# Power.net
KiCad netlist of a schematic drawn in Altium Designer
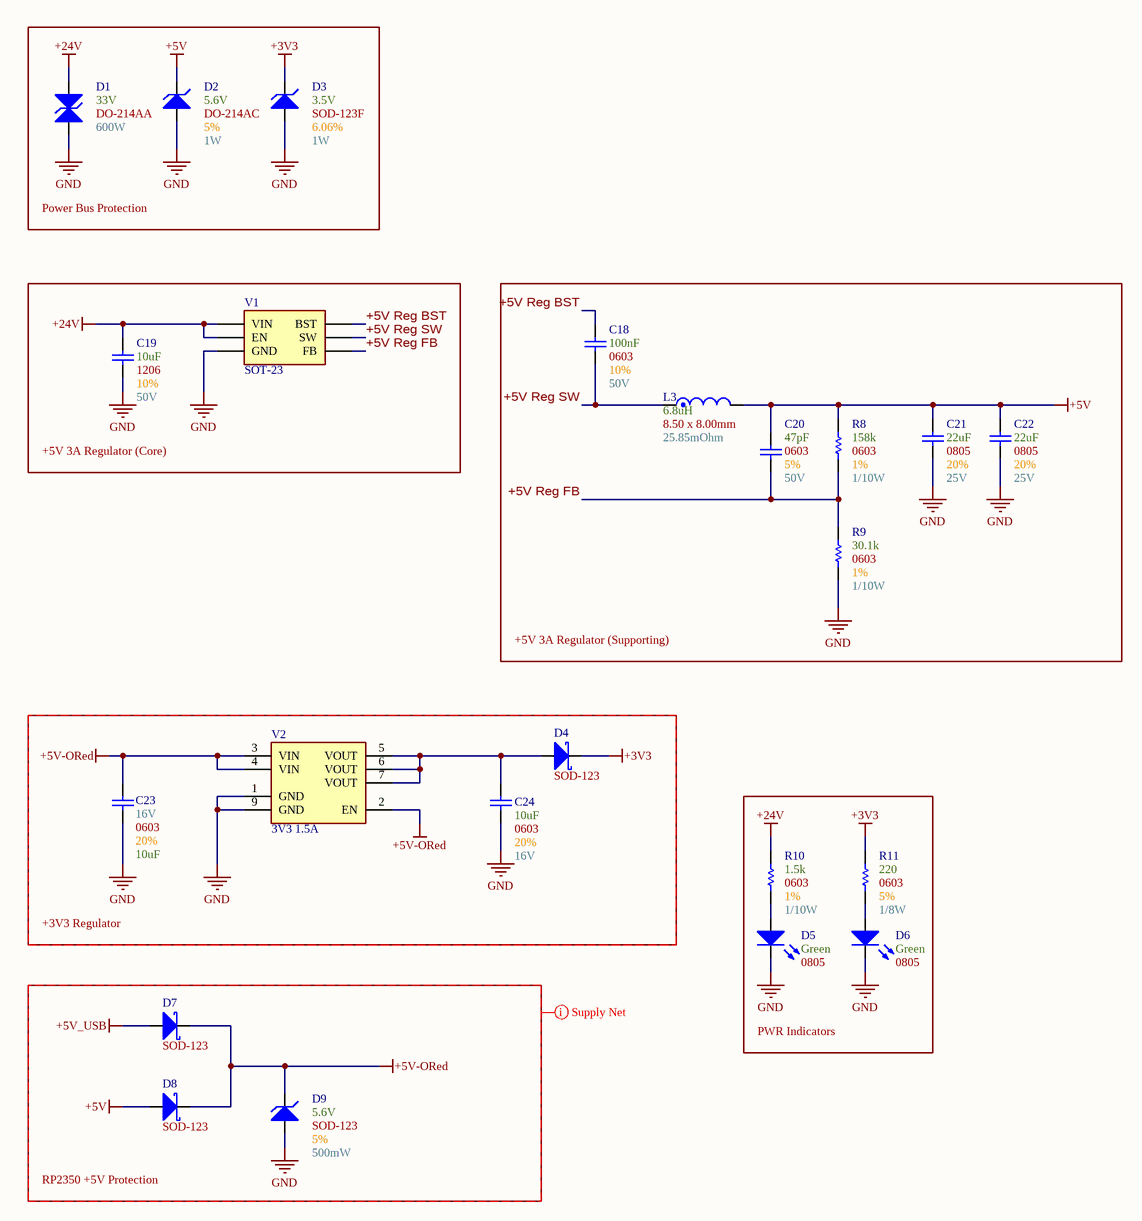
[diagram p0: Power.SchDoc]

(export (version "E")
  (design (tool "Eeschema 10.0.6"))
  (components
    (comp (ref "C18")
      (value "[Cap] 0603 0.1uF 10% 50V")
      (footprint "[Cap] SMD 0603")
      (description "CL10B104KB8NNNC")
      (fields
        (field (name "MAX VOLTAGE") "50V")
        (field (name "SIZE PACKAGE") "0603")
        (field (name "TOLERANCE") "10%")
        (field (name "CAPACITANCE") "100nF")
      )
      (libsource (lib "Capacitors") (part "[Cap] 0603 0.1uF 10% 50V"))
    )
    (comp (ref "C19")
      (value "[Cap] 1206 10uF 20% 50V")
      (footprint "[Cap] SMD 1206")
      (description "CGA5L3X5R1H106M160AB")
      (fields
        (field (name "MAX VOLTAGE") "50V")
        (field (name "SIZE PACKAGE") "1206")
        (field (name "TOLERANCE") "10%")
        (field (name "CAPACITANCE") "10uF")
      )
      (libsource (lib "Capacitors") (part "[Cap] 1206 10uF 20% 50V"))
    )
    (comp (ref "C20")
      (value "[Cap] 0603 47pF 5% 50V")
      (footprint "[Cap] SMD 0603")
      (description "CL10C470JB8NNNC")
      (fields
        (field (name "MAX VOLTAGE") "50V")
        (field (name "SIZE PACKAGE") "0603")
        (field (name "TOLERANCE") "5%")
        (field (name "CAPACITANCE") "47pF")
      )
      (libsource (lib "Capacitors") (part "[Cap] 0603 47pF 5% 50V"))
    )
    (comp (ref "C21")
      (value "[Cap] 0805 22uF 20% 25V")
      (footprint "[Cap] SMD 0805")
      (description "CL21A226MAYNNWE")
      (fields
        (field (name "MAX VOLTAGE") "25V")
        (field (name "SIZE PACKAGE") "0805")
        (field (name "TOLERANCE") "20%")
        (field (name "CAPACITANCE") "22uF")
      )
      (libsource (lib "Capacitors") (part "[Cap] 0805 22uF 20% 25V"))
    )
    (comp (ref "C22")
      (value "[Cap] 0805 22uF 20% 25V")
      (footprint "[Cap] SMD 0805")
      (description "CL21A226MAYNNWE")
      (fields
        (field (name "MAX VOLTAGE") "25V")
        (field (name "SIZE PACKAGE") "0805")
        (field (name "TOLERANCE") "20%")
        (field (name "CAPACITANCE") "22uF")
      )
      (libsource (lib "Capacitors") (part "[Cap] 0805 22uF 20% 25V"))
    )
    (comp (ref "C23")
      (value "[Cap] 0603 10uF 20% 16V")
      (footprint "[Cap] SMD 0603")
      (description "GRM188C81C106MA73D")
      (fields
        (field (name "MAX VOLTAGE") "16V")
        (field (name "SIZE PACKAGE") "0603")
        (field (name "TOLERANCE") "20%")
        (field (name "CAPACITANCE") "10uF")
      )
      (libsource (lib "Capacitors") (part "[Cap] 0603 10uF 20% 16V"))
    )
    (comp (ref "C24")
      (value "[Cap] 0603 10uF 20% 16V")
      (footprint "[Cap] SMD 0603")
      (description "GRM188C81C106MA73D")
      (fields
        (field (name "MAX VOLTAGE") "16V")
        (field (name "SIZE PACKAGE") "0603")
        (field (name "TOLERANCE") "20%")
        (field (name "CAPACITANCE") "10uF")
      )
      (libsource (lib "Capacitors") (part "[Cap] 0603 10uF 20% 16V"))
    )
    (comp (ref "D1")
      (value "DO-214AA")
      (footprint "DO-214AA")
      (description "SMBJ33CA")
      (fields (field (name "WATTAGE") "600W") (field (name "OPTIMAL ZENER VOLTAGE") "33V"))
      (libsource (lib "Diodes") (part "[TVS] SMBJ33CA"))
    )
    (comp (ref "D2")
      (value "DO-214AC")
      (footprint "DO-214AC")
      (description "SMAZ5V6-13-F")
      (fields
        (field (name "TOLERANCE") "5%")
        (field (name "WATTAGE") "1W")
        (field (name "OPTIMAL ZENER VOLTAGE") "5.6V")
      )
      (libsource (lib "Diodes") (part "[Zener] SMD 5.6V 1W 5%"))
    )
    (comp (ref "D3")
      (value "SOD-123F")
      (footprint "SOD-123F")
      (description "KDZVTR3.3B")
      (fields
        (field (name "TOLERANCE") "6.06%")
        (field (name "WATTAGE") "1W")
        (field (name "OPTIMAL ZENER VOLTAGE") "3.5V")
      )
      (libsource (lib "Diodes") (part "[Zener] SMD 3.5V 1W 6%"))
    )
    (comp (ref "D4")
      (value "SOD123")
      (footprint "SOD-123")
      (description "B5819W-TP")
      (libsource (lib "Diodes") (part "[Schottky] SMD 40V 1A"))
    )
    (comp (ref "D5")
      (value "[LED] SMD 0805 Green")
      (footprint "[LED] SMD 0805")
      (description "LG R971-KN-1-0-20-R18")
      (fields (field (name "COLOR") "Green") (field (name "SIZE PACKAGE") "0805"))
      (libsource (lib "LEDs") (part "[LED] SMD 0805 Green"))
    )
    (comp (ref "D6")
      (value "[LED] SMD 0805 Green")
      (footprint "[LED] SMD 0805")
      (description "LG R971-KN-1-0-20-R18")
      (fields (field (name "COLOR") "Green") (field (name "SIZE PACKAGE") "0805"))
      (libsource (lib "LEDs") (part "[LED] SMD 0805 Green"))
    )
    (comp (ref "D7")
      (value "SOD123")
      (footprint "SOD-123")
      (description "B5819W-TP")
      (libsource (lib "Diodes") (part "[Schottky] SMD 40V 1A"))
    )
    (comp (ref "D8")
      (value "SOD123")
      (footprint "SOD-123")
      (description "B5819W-TP")
      (libsource (lib "Diodes") (part "[Schottky] SMD 40V 1A"))
    )
    (comp (ref "D9")
      (value "SOD-123")
      (footprint "SOD-123")
      (description "CMHZ5232B TR PBFREE")
      (fields
        (field (name "TOLERANCE") "5%")
        (field (name "WATTAGE") "500mW")
        (field (name "OPTIMAL ZENER VOLTAGE") "5.6V")
      )
      (libsource (lib "Diodes") (part "[Zener] SMD 5.6V 1/2W 5%"))
    )
    (comp (ref "L3")
      (value "[6.8uH] SMD Nonstandard 6.9A")
      (footprint "[6.8uH] SMD Nonstandard 6.9A")
      (description "ETQ-P4M6R8KVK")
      (fields
        (field (name "DC RESISTANCE") "25.85mOhm")
        (field (name "PACKAGE") "8.50 x 8.00mm")
        (field (name "INDUCTANCE") "6.8uH")
      )
      (libsource (lib "Inductors") (part "[6.8uH] SMD Nonstandard 6.9A"))
    )
    (comp (ref "R8")
      (value "[158k] SMD 0603 1% 1/10W")
      (footprint "[Res] SMD 0603")
      (description "RC0603FR-07158KL")
      (fields
        (field (name "WATTAGE") "1/10W")
        (field (name "TOLERANCE") "1%")
        (field (name "RESISTANCE") "158k")
        (field (name "SIZE PACKAGE") "0603")
      )
      (libsource (lib "Resistors") (part "[158k] SMD 0603 1% 1/10W"))
    )
    (comp (ref "R9")
      (value "[30.1k] SMD 0603 1% 1/10W")
      (footprint "[Res] SMD 0603")
      (description "RC0603FR-0730K1L")
      (fields
        (field (name "WATTAGE") "1/10W")
        (field (name "TOLERANCE") "1%")
        (field (name "RESISTANCE") "30.1k")
        (field (name "SIZE PACKAGE") "0603")
      )
      (libsource (lib "Resistors") (part "[30.1k] SMD 0603 1% 1/10W"))
    )
    (comp (ref "R10")
      (value "[1.5k] SMD 0603 1% 1/10W")
      (footprint "[Res] SMD 0603")
      (description "CR0603-FX-1501ELF")
      (fields
        (field (name "WATTAGE") "1/10W")
        (field (name "TOLERANCE") "1%")
        (field (name "RESISTANCE") "1.5k")
        (field (name "SIZE PACKAGE") "0603")
      )
      (libsource (lib "Resistors") (part "[1.5k] SMD 0603 1% 1/10W"))
    )
    (comp (ref "R11")
      (value "[220] SMD 0603 5% 1/10W")
      (footprint "[Res] SMD 0603")
      (description "RK73B1JTTD221J")
      (fields
        (field (name "WATTAGE") "1/8W")
        (field (name "TOLERANCE") "5%")
        (field (name "RESISTANCE") "220")
        (field (name "SIZE PACKAGE") "0603")
      )
      (libsource (lib "Resistors") (part "[220] SMD 0603 5% 1/10W"))
    )
    (comp (ref "V1")
      (value "SOT-23")
      (footprint "SOT-23")
      (description "AP63301WU-7")
      (libsource (lib "Voltage Regulators") (part "[Switching] SMD 0.8-31V 3A"))
    )
    (comp (ref "V2")
      (value "3V3 1.5A")
      (footprint "[Linear] 3V3 1.5A")
      (description "AP7362A-33SP-13")
      (libsource (lib "Voltage Regulators") (part "[Linear] SMD 3V3 1.5A"))
    )
  )
  (nets
    (net (code "1") (name "+3V3") (class "Default")
      (node (ref "D3") (pin "1") (pinfunction "K_1") (pintype "passive"))
      (node (ref "D4") (pin "1") (pinfunction "K_1") (pintype "passive"))
      (node (ref "R11") (pin "2") (pinfunction "2_2") (pintype "passive"))
    )
    (net (code "2") (name "+5V") (class "Default")
      (node (ref "C20") (pin "2") (pinfunction "2_2") (pintype "passive"))
      (node (ref "C21") (pin "2") (pinfunction "2_2") (pintype "passive"))
      (node (ref "C22") (pin "2") (pinfunction "2_2") (pintype "passive"))
      (node (ref "D2") (pin "1") (pinfunction "K_1") (pintype "passive"))
      (node (ref "D8") (pin "2") (pinfunction "A_2") (pintype "passive"))
      (node (ref "L3") (pin "2") (pinfunction "2_2") (pintype "passive"))
      (node (ref "R8") (pin "2") (pinfunction "2_2") (pintype "passive"))
    )
    (net (code "3") (name "+5V-ORed") (class "Default")
      (node (ref "C23") (pin "2") (pinfunction "2_2") (pintype "passive"))
      (node (ref "D7") (pin "1") (pinfunction "K_1") (pintype "passive"))
      (node (ref "D8") (pin "1") (pinfunction "K_1") (pintype "passive"))
      (node (ref "D9") (pin "1") (pinfunction "K_1") (pintype "passive"))
      (node (ref "V2") (pin "2") (pinfunction "EN_2") (pintype "passive"))
      (node (ref "V2") (pin "3") (pinfunction "VIN_3") (pintype "passive"))
      (node (ref "V2") (pin "4") (pinfunction "VIN_4") (pintype "passive"))
    )
    (net (code "4") (name "+5V_USB") (class "Default")
      (node (ref "D7") (pin "2") (pinfunction "A_2") (pintype "passive"))
    )
    (net (code "5") (name "+24V") (class "Default")
      (node (ref "C19") (pin "2") (pinfunction "2_2") (pintype "passive"))
      (node (ref "D1") (pin "2") (pinfunction "K_2") (pintype "passive"))
      (node (ref "R10") (pin "2") (pinfunction "2_2") (pintype "passive"))
      (node (ref "V1") (pin "2") (pinfunction "EN_2") (pintype "passive"))
      (node (ref "V1") (pin "3") (pinfunction "VIN_3") (pintype "passive"))
    )
    (net (code "6") (name "/+5V Reg BST") (class "Default")
      (node (ref "C18") (pin "2") (pinfunction "2_2") (pintype "passive"))
      (node (ref "V1") (pin "6") (pinfunction "BST_6") (pintype "passive"))
    )
    (net (code "7") (name "/+5V Reg FB") (class "Default")
      (node (ref "C20") (pin "1") (pinfunction "1_1") (pintype "passive"))
      (node (ref "R8") (pin "1") (pinfunction "1_1") (pintype "passive"))
      (node (ref "R9") (pin "2") (pinfunction "2_2") (pintype "passive"))
      (node (ref "V1") (pin "1") (pinfunction "FB_1") (pintype "passive"))
    )
    (net (code "8") (name "/+5V Reg SW") (class "Default")
      (node (ref "C18") (pin "1") (pinfunction "1_1") (pintype "passive"))
      (node (ref "L3") (pin "1") (pinfunction "1_1") (pintype "passive"))
      (node (ref "V1") (pin "5") (pinfunction "SW_5") (pintype "passive"))
    )
    (net (code "9") (name "GND") (class "Default")
      (node (ref "C19") (pin "1") (pinfunction "1_1") (pintype "passive"))
      (node (ref "C21") (pin "1") (pinfunction "1_1") (pintype "passive"))
      (node (ref "C22") (pin "1") (pinfunction "1_1") (pintype "passive"))
      (node (ref "C23") (pin "1") (pinfunction "1_1") (pintype "passive"))
      (node (ref "C24") (pin "1") (pinfunction "1_1") (pintype "passive"))
      (node (ref "D1") (pin "1") (pinfunction "A_1") (pintype "passive"))
      (node (ref "D2") (pin "2") (pinfunction "A_2") (pintype "passive"))
      (node (ref "D3") (pin "2") (pinfunction "A_2") (pintype "passive"))
      (node (ref "D5") (pin "2") (pinfunction "Cathode_2") (pintype "passive"))
      (node (ref "D6") (pin "2") (pinfunction "Cathode_2") (pintype "passive"))
      (node (ref "D9") (pin "2") (pinfunction "A_2") (pintype "passive"))
      (node (ref "R9") (pin "1") (pinfunction "1_1") (pintype "passive"))
      (node (ref "V1") (pin "4") (pinfunction "GND_4") (pintype "passive"))
      (node (ref "V2") (pin "1") (pinfunction "GND_1") (pintype "passive"))
      (node (ref "V2") (pin "9") (pinfunction "GND_9") (pintype "passive"))
    )
    (net (code "10") (name "Net-(D4-A)") (class "Default")
      (node (ref "C24") (pin "2") (pinfunction "2_2") (pintype "passive"))
      (node (ref "D4") (pin "2") (pinfunction "A_2") (pintype "passive"))
      (node (ref "V2") (pin "5") (pinfunction "VOUT_5") (pintype "passive"))
      (node (ref "V2") (pin "6") (pinfunction "VOUT_6") (pintype "passive"))
      (node (ref "V2") (pin "7") (pinfunction "VOUT_7") (pintype "passive"))
    )
    (net (code "11") (name "Net-(D5-Anode)") (class "Default")
      (node (ref "D5") (pin "1") (pinfunction "Anode_1") (pintype "passive"))
      (node (ref "R10") (pin "1") (pinfunction "1_1") (pintype "passive"))
    )
    (net (code "12") (name "Net-(D6-Anode)") (class "Default")
      (node (ref "D6") (pin "1") (pinfunction "Anode_1") (pintype "passive"))
      (node (ref "R11") (pin "1") (pinfunction "1_1") (pintype "passive"))
    )
  )
)
